# Power_Distribution_-_IO_Expander.net
KiCad netlist of a schematic drawn in Altium Designer
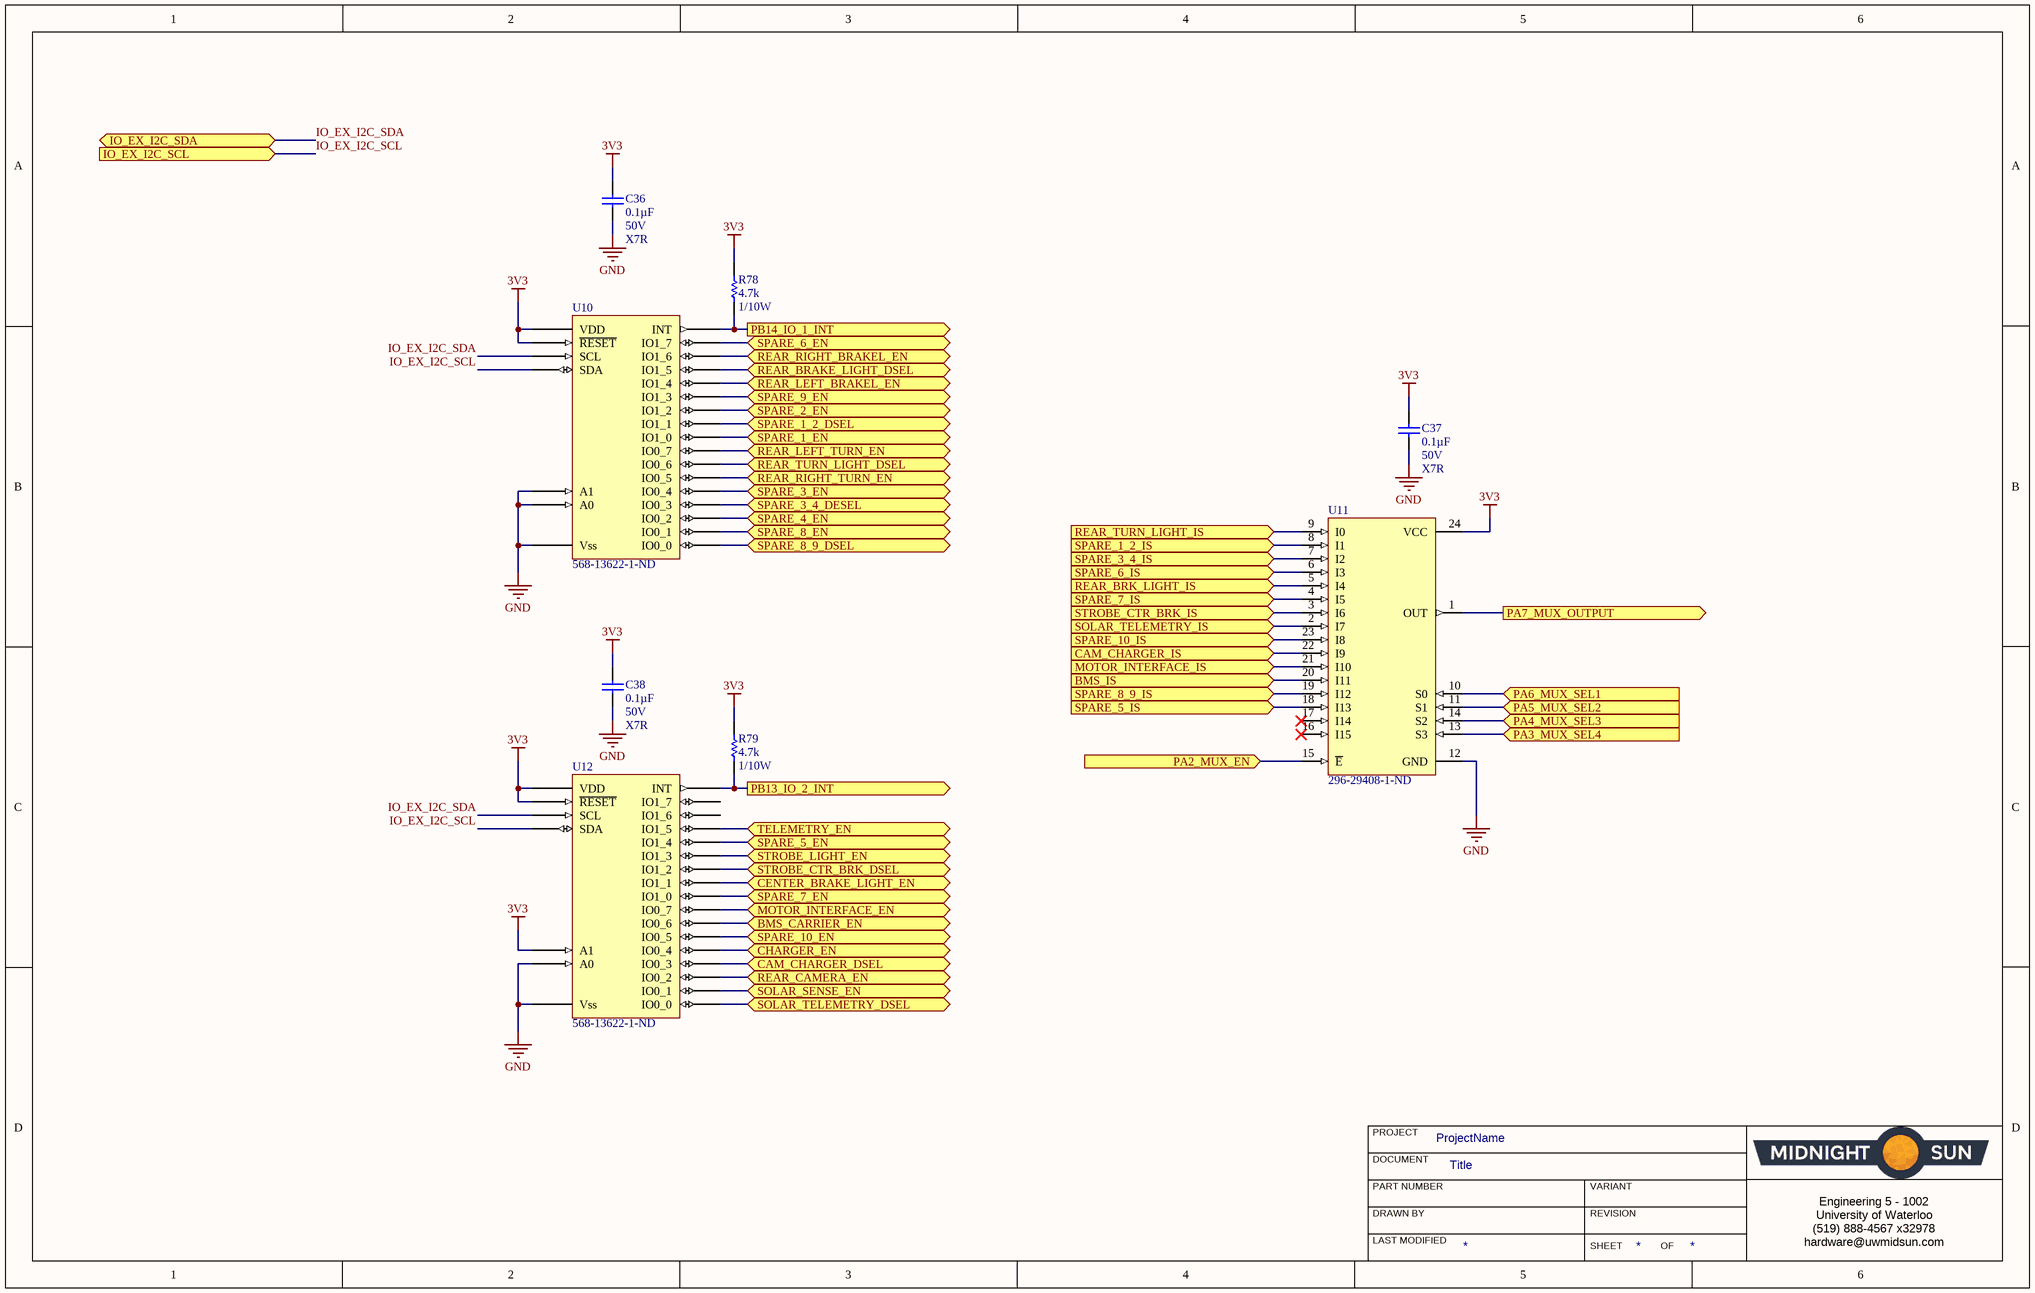
[diagram p0: Power Distribution - IO Expander.SchDoc]

(export (version "E")
  (design (tool "Eeschema 10.0.6"))
  (components
    (comp (ref "C36")
      (value "CAP CER 0.1UF 50V 10% X7R 0603")
      (footprint "CAP, 0603")
      (description "0.10µF ±10% 50V Ceramic Capacitor X7R 0603 (1608 Metric)")
      (fields
        (field (name "TOLERANCE") "±10%")
        (field (name "CAPACITANCE") "0.1µF")
        (field (name "VOLTAGE") "50V")
        (field (name "TEMPERATURE COEFFICIENT") "X7R")
      )
      (libsource (lib "Schematic Diagrams") (part "CAP CER 0.1UF 50V 10% X7R 0603"))
    )
    (comp (ref "C37")
      (value "CAP CER 0.1UF 50V 10% X7R 0603")
      (footprint "CAP, 0603")
      (description "0.10µF ±10% 50V Ceramic Capacitor X7R 0603 (1608 Metric)")
      (fields
        (field (name "TOLERANCE") "±10%")
        (field (name "CAPACITANCE") "0.1µF")
        (field (name "VOLTAGE") "50V")
        (field (name "TEMPERATURE COEFFICIENT") "X7R")
      )
      (libsource (lib "Schematic Diagrams") (part "CAP CER 0.1UF 50V 10% X7R 0603"))
    )
    (comp (ref "C38")
      (value "CAP CER 0.1UF 50V 10% X7R 0603")
      (footprint "CAP, 0603")
      (description "0.10µF ±10% 50V Ceramic Capacitor X7R 0603 (1608 Metric)")
      (fields
        (field (name "TOLERANCE") "±10%")
        (field (name "CAPACITANCE") "0.1µF")
        (field (name "VOLTAGE") "50V")
        (field (name "TEMPERATURE COEFFICIENT") "X7R")
      )
      (libsource (lib "Schematic Diagrams") (part "CAP CER 0.1UF 50V 10% X7R 0603"))
    )
    (comp (ref "R78")
      (value "RES 4.7K OHM 1% 1/10W 0603")
      (footprint "RES, 0603")
      (description "4.7k Ohm ±1% 0.1W, 1/10W Chip Resistor 0603 (1608 Metric) Moisture Resistant Thick Film")
      (fields
        (field (name "TOLERANCE") "±1%")
        (field (name "RESISTANCE (OHMS)") "4.7k")
        (field (name "POWER (WATTS)") "1/10W")
      )
      (libsource (lib "Schematic Diagrams") (part "RES 4.7K OHM 1% 1/10W 0603"))
    )
    (comp (ref "R79")
      (value "RES 4.7K OHM 1% 1/10W 0603")
      (footprint "RES, 0603")
      (description "4.7k Ohm ±1% 0.1W, 1/10W Chip Resistor 0603 (1608 Metric) Moisture Resistant Thick Film")
      (fields
        (field (name "TOLERANCE") "±1%")
        (field (name "RESISTANCE (OHMS)") "4.7k")
        (field (name "POWER (WATTS)") "1/10W")
      )
      (libsource (lib "Schematic Diagrams") (part "RES 4.7K OHM 1% 1/10W 0603"))
    )
    (comp (ref "U10")
      (value "16-BIT I2C-BUS AND SMBUS LOW POW")
      (footprint "SOP127P600-8N")
      (description "I/O Expander 16 I²C, SMBus 400kHz 24-TSSOP")
      (fields (field (name "SUPPLIER PART NUMBER 1") "568-13622-1-ND"))
      (libsource (lib "Schematic Diagrams") (part "16-BIT I2C-BUS AND SMBUS LOW POW"))
    )
    (comp (ref "U11")
      (value "IC MUX/DEMUX 1X16 24SSOP")
      (footprint "SOP127P1030X265-24N")
      (description "1 Circuit IC Switch 16:1 160 Ohm 24-SOIC")
      (fields
        (field (name "MANUFACTURER") "Texas Instruments")
        (field (name "MANUFACTURER PART NUMBER") "CD74HC4067M96")
        (field (name "SUPPLIER PART NUMBER 1") "296-29408-1-ND")
      )
      (libsource (lib "Schematic Diagrams") (part "IC MUX/DEMUX 1X16 24SSOP"))
    )
    (comp (ref "U12")
      (value "16-BIT I2C-BUS AND SMBUS LOW POW")
      (footprint "SOP127P600-8N")
      (description "I/O Expander 16 I²C, SMBus 400kHz 24-TSSOP")
      (fields (field (name "SUPPLIER PART NUMBER 1") "568-13622-1-ND"))
      (libsource (lib "Schematic Diagrams") (part "16-BIT I2C-BUS AND SMBUS LOW POW"))
    )
  )
  (nets
    (net (code "1") (name "/BMS_CARRIER_EN") (class "Default")
      (node (ref "U12") (pin "10") (pinfunction "IO0_6_10") (pintype "bidirectional"))
    )
    (net (code "2") (name "/BMS_IS") (class "Default")
      (node (ref "U11") (pin "20") (pinfunction "I11_20") (pintype "input"))
    )
    (net (code "3") (name "/CAM_CHARGER_DSEL") (class "Default")
      (node (ref "U12") (pin "7") (pinfunction "IO0_3_7") (pintype "bidirectional"))
    )
    (net (code "4") (name "/CAM_CHARGER_IS") (class "Default")
      (node (ref "U11") (pin "22") (pinfunction "I9_22") (pintype "input"))
    )
    (net (code "5") (name "/CENTER_BRAKE_LIGHT_EN") (class "Default")
      (node (ref "U12") (pin "14") (pinfunction "IO1_1_14") (pintype "bidirectional"))
    )
    (net (code "6") (name "/CHARGER_EN") (class "Default")
      (node (ref "U12") (pin "8") (pinfunction "IO0_4_8") (pintype "bidirectional"))
    )
    (net (code "7") (name "/IO_EX_I2C_SCL") (class "Default")
      (node (ref "U10") (pin "23") (pinfunction "SDA_23") (pintype "bidirectional"))
      (node (ref "U12") (pin "23") (pinfunction "SDA_23") (pintype "bidirectional"))
    )
    (net (code "8") (name "/IO_EX_I2C_SDA") (class "Default")
      (node (ref "U10") (pin "22") (pinfunction "SCL_22") (pintype "input"))
      (node (ref "U12") (pin "22") (pinfunction "SCL_22") (pintype "input"))
    )
    (net (code "9") (name "/MOTOR_INTERFACE_EN") (class "Default")
      (node (ref "U12") (pin "11") (pinfunction "IO0_7_11") (pintype "bidirectional"))
    )
    (net (code "10") (name "/MOTOR_INTERFACE_IS") (class "Default")
      (node (ref "U11") (pin "21") (pinfunction "I10_21") (pintype "input"))
    )
    (net (code "11") (name "/PA2_MUX_EN") (class "Default")
      (node (ref "U11") (pin "15") (pinfunction "~{E}_15") (pintype "input"))
    )
    (net (code "12") (name "/PA3_MUX_SEL4") (class "Default")
      (node (ref "U11") (pin "13") (pinfunction "S3_13") (pintype "input"))
    )
    (net (code "13") (name "/PA4_MUX_SEL3") (class "Default")
      (node (ref "U11") (pin "14") (pinfunction "S2_14") (pintype "input"))
    )
    (net (code "14") (name "/PA5_MUX_SEL2") (class "Default")
      (node (ref "U11") (pin "11") (pinfunction "S1_11") (pintype "input"))
    )
    (net (code "15") (name "/PA6_MUX_SEL1") (class "Default")
      (node (ref "U11") (pin "10") (pinfunction "S0_10") (pintype "input"))
    )
    (net (code "16") (name "/PA7_MUX_OUTPUT") (class "Default")
      (node (ref "U11") (pin "1") (pinfunction "OUT_1") (pintype "output"))
    )
    (net (code "17") (name "/PB13_IO_2_INT") (class "Default")
      (node (ref "R79") (pin "2") (pinfunction "2_2") (pintype "passive"))
      (node (ref "U12") (pin "1") (pinfunction "INT_1") (pintype "output"))
    )
    (net (code "18") (name "/PB14_IO_1_INT") (class "Default")
      (node (ref "R78") (pin "2") (pinfunction "2_2") (pintype "passive"))
      (node (ref "U10") (pin "1") (pinfunction "INT_1") (pintype "output"))
    )
    (net (code "19") (name "/REAR_BRAKE_LIGHT_DSEL") (class "Default")
      (node (ref "U10") (pin "18") (pinfunction "IO1_5_18") (pintype "bidirectional"))
    )
    (net (code "20") (name "/REAR_BRK_LIGHT_IS") (class "Default")
      (node (ref "U11") (pin "5") (pinfunction "I4_5") (pintype "input"))
    )
    (net (code "21") (name "/REAR_CAMERA_EN") (class "Default")
      (node (ref "U12") (pin "6") (pinfunction "IO0_2_6") (pintype "bidirectional"))
    )
    (net (code "22") (name "/REAR_LEFT_BRAKEL_EN") (class "Default")
      (node (ref "U10") (pin "17") (pinfunction "IO1_4_17") (pintype "bidirectional"))
    )
    (net (code "23") (name "/REAR_LEFT_TURN_EN") (class "Default")
      (node (ref "U10") (pin "11") (pinfunction "IO0_7_11") (pintype "bidirectional"))
    )
    (net (code "24") (name "/REAR_RIGHT_BRAKEL_EN") (class "Default")
      (node (ref "U10") (pin "19") (pinfunction "IO1_6_19") (pintype "bidirectional"))
    )
    (net (code "25") (name "/REAR_RIGHT_TURN_EN") (class "Default")
      (node (ref "U10") (pin "9") (pinfunction "IO0_5_9") (pintype "bidirectional"))
    )
    (net (code "26") (name "/REAR_TURN_LIGHT_DSEL") (class "Default")
      (node (ref "U10") (pin "10") (pinfunction "IO0_6_10") (pintype "bidirectional"))
    )
    (net (code "27") (name "/REAR_TURN_LIGHT_IS") (class "Default")
      (node (ref "U11") (pin "9") (pinfunction "I0_9") (pintype "input"))
    )
    (net (code "28") (name "/SOLAR_SENSE_EN") (class "Default")
      (node (ref "U12") (pin "5") (pinfunction "IO0_1_5") (pintype "bidirectional"))
    )
    (net (code "29") (name "/SOLAR_TELEMETRY_DSEL") (class "Default")
      (node (ref "U12") (pin "4") (pinfunction "IO0_0_4") (pintype "bidirectional"))
    )
    (net (code "30") (name "/SOLAR_TELEMETRY_IS") (class "Default")
      (node (ref "U11") (pin "2") (pinfunction "I7_2") (pintype "input"))
    )
    (net (code "31") (name "/SPARE_1_2_DSEL") (class "Default")
      (node (ref "U10") (pin "14") (pinfunction "IO1_1_14") (pintype "bidirectional"))
    )
    (net (code "32") (name "/SPARE_1_2_IS") (class "Default")
      (node (ref "U11") (pin "8") (pinfunction "I1_8") (pintype "input"))
    )
    (net (code "33") (name "/SPARE_1_EN") (class "Default")
      (node (ref "U10") (pin "13") (pinfunction "IO1_0_13") (pintype "bidirectional"))
    )
    (net (code "34") (name "/SPARE_2_EN") (class "Default")
      (node (ref "U10") (pin "15") (pinfunction "IO1_2_15") (pintype "bidirectional"))
    )
    (net (code "35") (name "/SPARE_3_4_DESEL") (class "Default")
      (node (ref "U10") (pin "7") (pinfunction "IO0_3_7") (pintype "bidirectional"))
    )
    (net (code "36") (name "/SPARE_3_4_IS") (class "Default")
      (node (ref "U11") (pin "7") (pinfunction "I2_7") (pintype "input"))
    )
    (net (code "37") (name "/SPARE_3_EN") (class "Default")
      (node (ref "U10") (pin "8") (pinfunction "IO0_4_8") (pintype "bidirectional"))
    )
    (net (code "38") (name "/SPARE_4_EN") (class "Default")
      (node (ref "U10") (pin "6") (pinfunction "IO0_2_6") (pintype "bidirectional"))
    )
    (net (code "39") (name "/SPARE_5_EN") (class "Default")
      (node (ref "U12") (pin "17") (pinfunction "IO1_4_17") (pintype "bidirectional"))
    )
    (net (code "40") (name "/SPARE_5_IS") (class "Default")
      (node (ref "U11") (pin "18") (pinfunction "I13_18") (pintype "input"))
    )
    (net (code "41") (name "/SPARE_6_EN") (class "Default")
      (node (ref "U10") (pin "20") (pinfunction "IO1_7_20") (pintype "bidirectional"))
    )
    (net (code "42") (name "/SPARE_6_IS") (class "Default")
      (node (ref "U11") (pin "6") (pinfunction "I3_6") (pintype "input"))
    )
    (net (code "43") (name "/SPARE_7_EN") (class "Default")
      (node (ref "U12") (pin "13") (pinfunction "IO1_0_13") (pintype "bidirectional"))
    )
    (net (code "44") (name "/SPARE_7_IS") (class "Default")
      (node (ref "U11") (pin "4") (pinfunction "I5_4") (pintype "input"))
    )
    (net (code "45") (name "/SPARE_8_9_DSEL") (class "Default")
      (node (ref "U10") (pin "4") (pinfunction "IO0_0_4") (pintype "bidirectional"))
    )
    (net (code "46") (name "/SPARE_8_9_IS") (class "Default")
      (node (ref "U11") (pin "19") (pinfunction "I12_19") (pintype "input"))
    )
    (net (code "47") (name "/SPARE_8_EN") (class "Default")
      (node (ref "U10") (pin "5") (pinfunction "IO0_1_5") (pintype "bidirectional"))
    )
    (net (code "48") (name "/SPARE_9_EN") (class "Default")
      (node (ref "U10") (pin "16") (pinfunction "IO1_3_16") (pintype "bidirectional"))
    )
    (net (code "49") (name "/SPARE_10_EN") (class "Default")
      (node (ref "U12") (pin "9") (pinfunction "IO0_5_9") (pintype "bidirectional"))
    )
    (net (code "50") (name "/SPARE_10_IS") (class "Default")
      (node (ref "U11") (pin "23") (pinfunction "I8_23") (pintype "input"))
    )
    (net (code "51") (name "/STROBE_CTR_BRK_DSEL") (class "Default")
      (node (ref "U12") (pin "15") (pinfunction "IO1_2_15") (pintype "bidirectional"))
    )
    (net (code "52") (name "/STROBE_CTR_BRK_IS") (class "Default")
      (node (ref "U11") (pin "3") (pinfunction "I6_3") (pintype "input"))
    )
    (net (code "53") (name "/STROBE_LIGHT_EN") (class "Default")
      (node (ref "U12") (pin "16") (pinfunction "IO1_3_16") (pintype "bidirectional"))
    )
    (net (code "54") (name "/TELEMETRY_EN") (class "Default")
      (node (ref "U12") (pin "18") (pinfunction "IO1_5_18") (pintype "bidirectional"))
    )
    (net (code "55") (name "3V3") (class "Default")
      (node (ref "C36") (pin "1") (pinfunction "1_1") (pintype "passive"))
      (node (ref "C37") (pin "1") (pinfunction "1_1") (pintype "passive"))
      (node (ref "C38") (pin "1") (pinfunction "1_1") (pintype "passive"))
      (node (ref "R78") (pin "1") (pinfunction "1_1") (pintype "passive"))
      (node (ref "R79") (pin "1") (pinfunction "1_1") (pintype "passive"))
      (node (ref "U10") (pin "24") (pinfunction "VDD_24") (pintype "power_in"))
      (node (ref "U10") (pin "3") (pinfunction "~{RESET}_3") (pintype "input"))
      (node (ref "U11") (pin "24") (pinfunction "VCC_24") (pintype "power_in"))
      (node (ref "U12") (pin "2") (pinfunction "A1_2") (pintype "input"))
      (node (ref "U12") (pin "24") (pinfunction "VDD_24") (pintype "power_in"))
      (node (ref "U12") (pin "3") (pinfunction "~{RESET}_3") (pintype "input"))
    )
    (net (code "56") (name "GND") (class "Default")
      (node (ref "C36") (pin "2") (pinfunction "2_2") (pintype "passive"))
      (node (ref "C37") (pin "2") (pinfunction "2_2") (pintype "passive"))
      (node (ref "C38") (pin "2") (pinfunction "2_2") (pintype "passive"))
      (node (ref "U10") (pin "12") (pinfunction "Vss_12") (pintype "power_in"))
      (node (ref "U10") (pin "2") (pinfunction "A1_2") (pintype "input"))
      (node (ref "U10") (pin "21") (pinfunction "A0_21") (pintype "input"))
      (node (ref "U11") (pin "12") (pinfunction "GND_12") (pintype "power_in"))
      (node (ref "U12") (pin "12") (pinfunction "Vss_12") (pintype "power_in"))
      (node (ref "U12") (pin "21") (pinfunction "A0_21") (pintype "input"))
    )
    (net (code "57") (name "unconnected-(U11-I14-Pad17)") (class "Default")
      (node (ref "U11") (pin "17") (pinfunction "I14_17") (pintype "input+no_connect"))
    )
    (net (code "58") (name "unconnected-(U11-I15-Pad16)") (class "Default")
      (node (ref "U11") (pin "16") (pinfunction "I15_16") (pintype "input+no_connect"))
    )
    (net (code "59") (name "unconnected-(U12-IO1_6-Pad19)") (class "Default")
      (node (ref "U12") (pin "19") (pinfunction "IO1_6_19") (pintype "bidirectional"))
    )
    (net (code "60") (name "unconnected-(U12-IO1_7-Pad20)") (class "Default")
      (node (ref "U12") (pin "20") (pinfunction "IO1_7_20") (pintype "bidirectional"))
    )
  )
)
